# V1_1001_REV2.net
KiCad netlist of a schematic drawn in Altium Designer
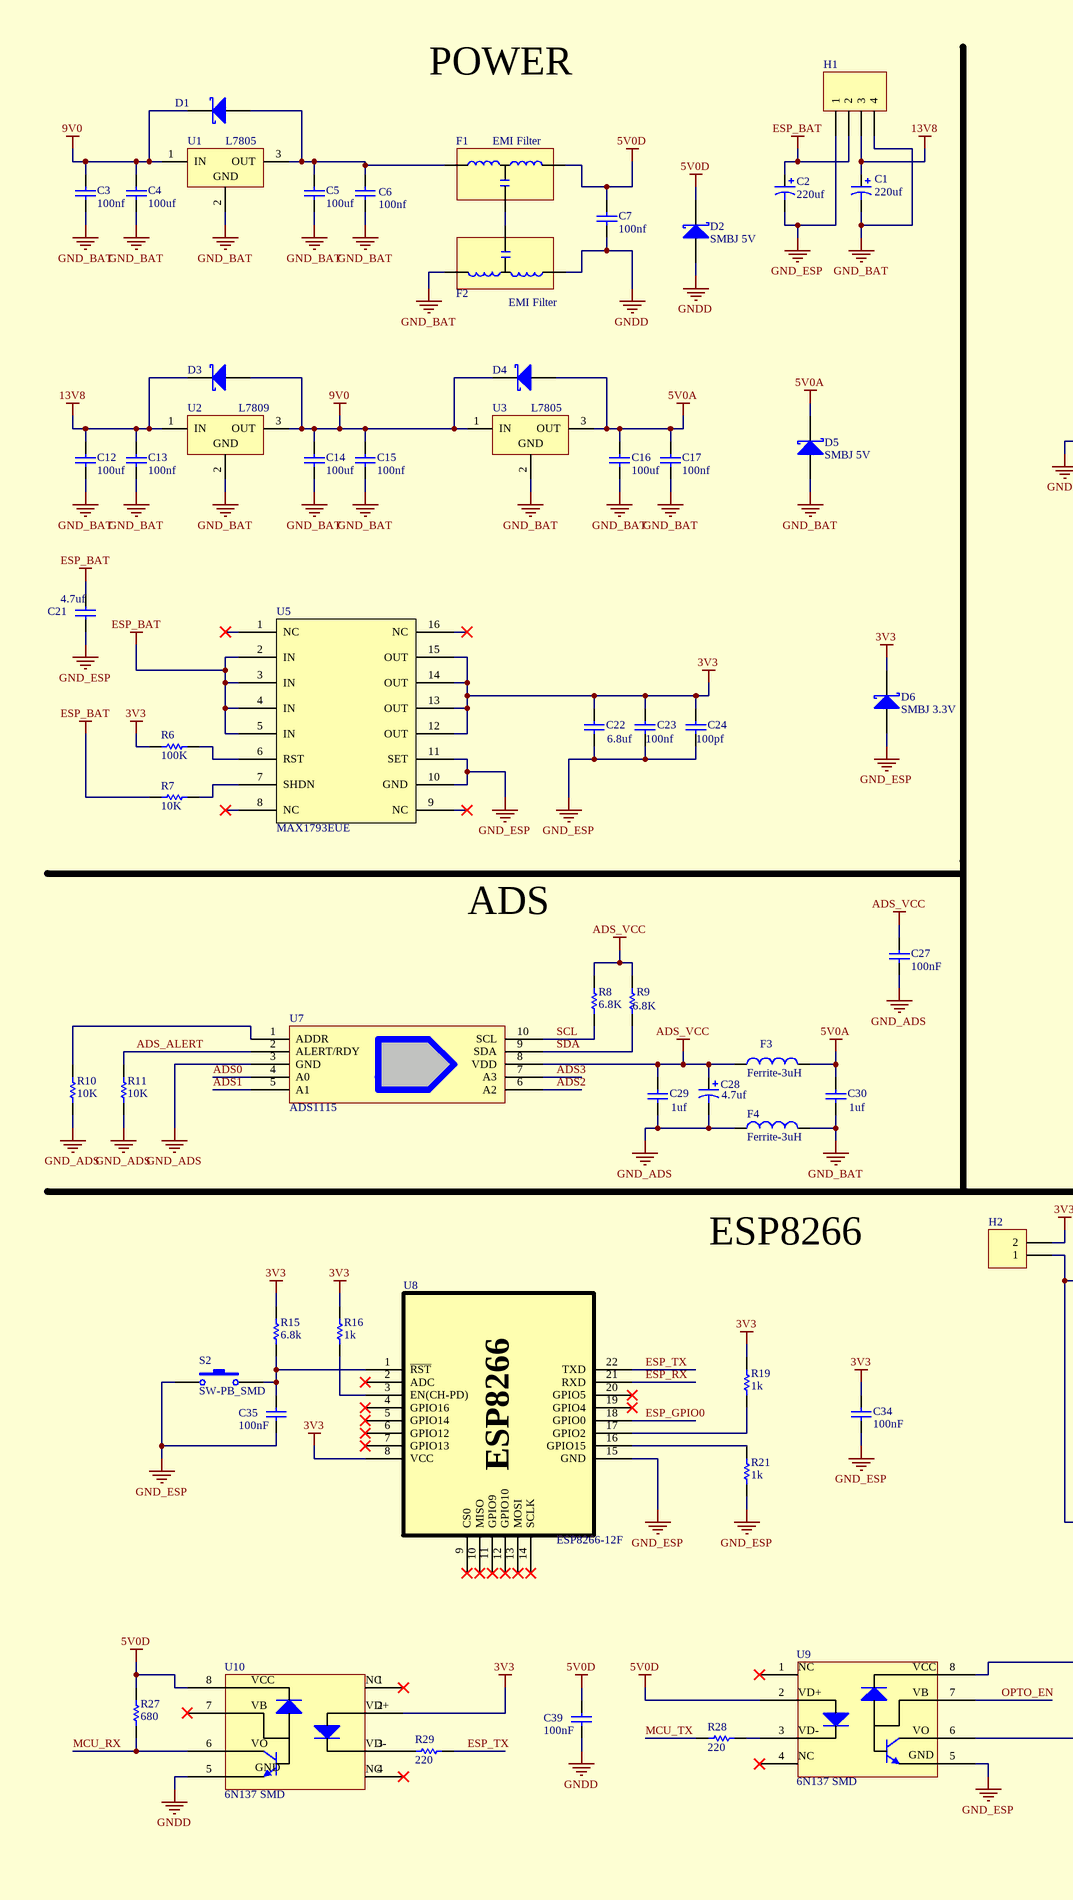
[diagram p0: V1_1001_REV2.SchDoc, left]
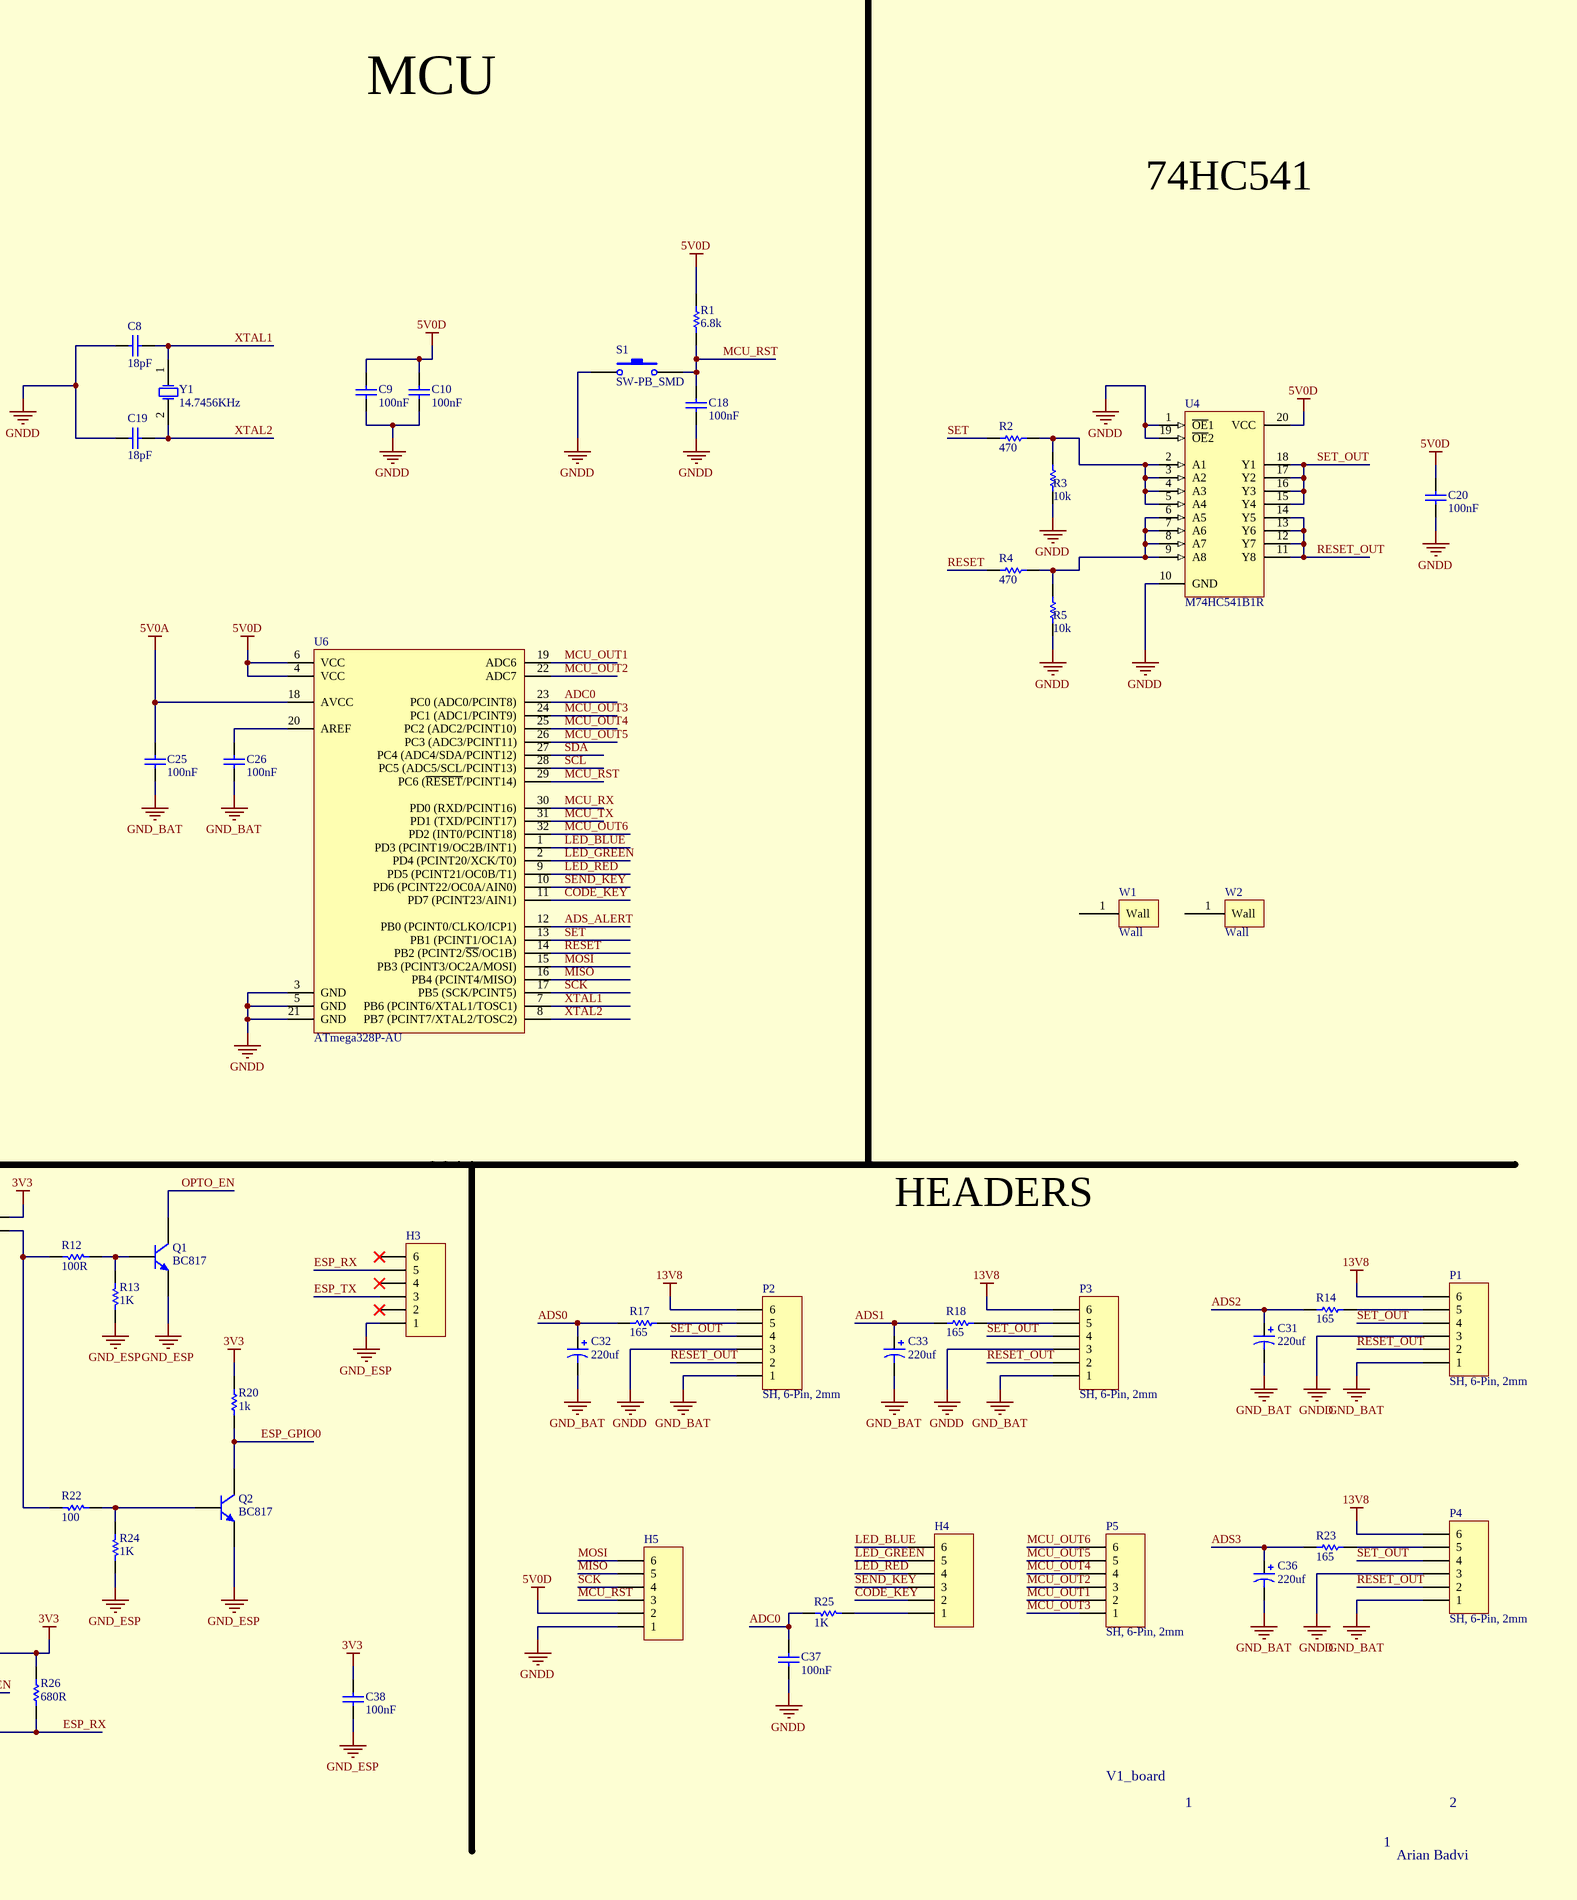
[diagram p1: V1_1001_REV2.SchDoc, right]

(export (version "E")
  (design (tool "Eeschema 10.0.6"))
  (components
    (comp (ref "C1")
      (value "220uf")
      (footprint "C_CYL_SMD2")
      (description "pol cap, Ele")
      (libsource (lib "Library") (part "Cap Pol"))
    )
    (comp (ref "C2")
      (value "220uf")
      (footprint "C_CYL_SMD2")
      (description "pol cap, Ele")
      (libsource (lib "Library") (part "Cap Pol"))
    )
    (comp (ref "C3")
      (value "100nf")
      (footprint "1206")
      (description "Capacitor, 1206")
      (libsource (lib "Miscellaneous Devices") (part "Cap"))
    )
    (comp (ref "C4")
      (value "100uf")
      (footprint "1206")
      (description "Capacitor, 1206")
      (libsource (lib "Miscellaneous Devices") (part "Cap"))
    )
    (comp (ref "C5")
      (value "100uf")
      (footprint "1206")
      (description "Capacitor, 1206")
      (libsource (lib "Miscellaneous Devices") (part "Cap"))
    )
    (comp (ref "C6")
      (value "100nf")
      (footprint "1206")
      (description "Capacitor, 1206")
      (libsource (lib "Miscellaneous Devices") (part "Cap"))
    )
    (comp (ref "C7")
      (value "100nf")
      (footprint "1206")
      (description "Capacitor, 1206")
      (libsource (lib "Miscellaneous Devices") (part "Cap"))
    )
    (comp (ref "C8")
      (value "18pF")
      (footprint "1206")
      (description "Capacitor")
      (libsource (lib "Miscellaneous Devices") (part "Cap"))
    )
    (comp (ref "C9")
      (value "100nF")
      (footprint "1206")
      (description "Capacitor")
      (libsource (lib "Miscellaneous Devices") (part "Cap"))
    )
    (comp (ref "C10")
      (value "100nF")
      (footprint "1206")
      (description "Capacitor")
      (libsource (lib "Miscellaneous Devices") (part "Cap"))
    )
    (comp (ref "C12")
      (value "100uf")
      (footprint "1206")
      (description "Capacitor, 1206")
      (libsource (lib "Miscellaneous Devices") (part "Cap"))
    )
    (comp (ref "C13")
      (value "100nf")
      (footprint "1206")
      (description "Capacitor, 1206")
      (libsource (lib "Miscellaneous Devices") (part "Cap"))
    )
    (comp (ref "C14")
      (value "100uf")
      (footprint "1206")
      (description "Capacitor, 1206")
      (libsource (lib "Miscellaneous Devices") (part "Cap"))
    )
    (comp (ref "C15")
      (value "100nf")
      (footprint "1206")
      (description "Capacitor, 1206")
      (libsource (lib "Miscellaneous Devices") (part "Cap"))
    )
    (comp (ref "C16")
      (value "100uf")
      (footprint "1206")
      (description "Capacitor, 1206")
      (libsource (lib "Miscellaneous Devices") (part "Cap"))
    )
    (comp (ref "C17")
      (value "100nf")
      (footprint "1206")
      (description "Capacitor, 1206")
      (libsource (lib "Miscellaneous Devices") (part "Cap"))
    )
    (comp (ref "C18")
      (value "100nF")
      (footprint "1206")
      (description "Capacitor")
      (libsource (lib "Miscellaneous Devices") (part "Cap"))
    )
    (comp (ref "C19")
      (value "18pF")
      (footprint "1206")
      (description "Capacitor")
      (libsource (lib "Miscellaneous Devices") (part "Cap"))
    )
    (comp (ref "C20")
      (value "100nF")
      (footprint "1206")
      (description "Capacitor, 1206, 100nf")
      (libsource (lib "Miscellaneous Devices") (part "Cap"))
    )
    (comp (ref "C21")
      (value "4.7uf")
      (footprint "1206")
      (description "Capacitor, 1206")
      (libsource (lib "Library") (part "Cap"))
    )
    (comp (ref "C22")
      (value "6.8uf")
      (footprint "1206")
      (description "Capacitor, 1206")
      (libsource (lib "Library") (part "Cap"))
    )
    (comp (ref "C23")
      (value "100nf")
      (footprint "1206")
      (description "Capacitor, 1206")
      (libsource (lib "Library") (part "Cap"))
    )
    (comp (ref "C24")
      (value "100pf")
      (footprint "1206")
      (description "Capacitor, 1206")
      (libsource (lib "Library") (part "Cap"))
    )
    (comp (ref "C25")
      (value "100nF")
      (footprint "1206")
      (description "Capacitor")
      (libsource (lib "Miscellaneous Devices") (part "Cap"))
    )
    (comp (ref "C26")
      (value "100nF")
      (footprint "1206")
      (description "Capacitor")
      (libsource (lib "Miscellaneous Devices") (part "Cap"))
    )
    (comp (ref "C27")
      (value "100nF")
      (footprint "1206")
      (description "Capacitor")
      (libsource (lib "Miscellaneous Devices") (part "Cap"))
    )
    (comp (ref "C28")
      (value "4.7uf")
      (footprint "CAP_SMD_A")
      (description "Tantalium Capacitor")
      (libsource (lib "Library") (part "Cap Pol"))
    )
    (comp (ref "C29")
      (value "1uf")
      (footprint "1206")
      (description "Capacitor, 1206")
      (libsource (lib "Library") (part "Cap"))
    )
    (comp (ref "C30")
      (value "1uf")
      (footprint "1206")
      (description "Capacitor, 1206")
      (libsource (lib "Library") (part "Cap"))
    )
    (comp (ref "C31")
      (value "220uf")
      (footprint "CAP_SMD_D")
      (description "pol cap, tan")
      (libsource (lib "Library") (part "Cap Pol"))
    )
    (comp (ref "C32")
      (value "220uf")
      (footprint "CAP_SMD_D")
      (description "pol cap, tan")
      (libsource (lib "Library") (part "Cap Pol"))
    )
    (comp (ref "C33")
      (value "220uf")
      (footprint "CAP_SMD_D")
      (description "pol cap, tan")
      (libsource (lib "Library") (part "Cap Pol"))
    )
    (comp (ref "C34")
      (value "100nF")
      (footprint "1206")
      (description "Capacitor")
      (libsource (lib "Miscellaneous Devices") (part "Cap"))
    )
    (comp (ref "C35")
      (value "100nF")
      (footprint "1206")
      (description "Capacitor")
      (libsource (lib "Miscellaneous Devices") (part "Cap"))
    )
    (comp (ref "C36")
      (value "220uf")
      (footprint "CAP_SMD_D")
      (description "pol cap, tan")
      (libsource (lib "Library") (part "Cap Pol"))
    )
    (comp (ref "C37")
      (value "100nF")
      (footprint "1206")
      (description "Capacitor")
      (libsource (lib "Miscellaneous Devices") (part "Cap"))
    )
    (comp (ref "C38")
      (value "100nF")
      (footprint "1206")
      (description "Capacitor")
      (libsource (lib "Miscellaneous Devices") (part "Cap"))
    )
    (comp (ref "C39")
      (value "100nF")
      (footprint "1206")
      (description "Capacitor, 1206")
      (libsource (lib "Miscellaneous Devices") (part "Cap"))
    )
    (comp (ref "D1")
      (value "D Schottky")
      (footprint "ZINER")
      (description "Schottky Diode, 1N4148")
      (libsource (lib "Miscellaneous Devices") (part "D Schottky"))
    )
    (comp (ref "D2")
      (value "SMBJ 5V")
      (footprint "TVS")
      (description "Schottky Rectifier")
      (libsource (lib "Miscellaneous Devices") (part "Diode 18TQ045"))
    )
    (comp (ref "D3")
      (value "D Schottky")
      (footprint "ZINER")
      (description "Schottky Diode, 1N4148")
      (libsource (lib "Miscellaneous Devices") (part "D Schottky"))
    )
    (comp (ref "D4")
      (value "D Schottky")
      (footprint "ZINER")
      (description "Schottky Diode, 1N4148")
      (libsource (lib "Miscellaneous Devices") (part "D Schottky"))
    )
    (comp (ref "D5")
      (value "SMBJ 5V")
      (footprint "TVS")
      (description "Schottky Rectifier")
      (libsource (lib "Miscellaneous Devices") (part "Diode 18TQ045"))
    )
    (comp (ref "D6")
      (value "SMBJ 3.3V")
      (footprint "TVS")
      (description "Schottky Rectifier")
      (libsource (lib "Miscellaneous Devices") (part "Diode 18TQ045"))
    )
    (comp (ref "F1")
      (value "EMI Filter")
      (footprint "HDR1X3")
      (libsource (lib "Library_v2") (part "EMI Filter"))
    )
    (comp (ref "F2") (value "EMI Filter") (footprint "HDR1X3") (libsource (lib "") (part "EMI Filter_1")))
    (comp (ref "F3")
      (value "Ferrite-3uH")
      (footprint "1206")
      (description "Inductor")
      (libsource (lib "Miscellaneous Devices") (part "Inductor"))
    )
    (comp (ref "F4")
      (value "Ferrite-3uH")
      (footprint "1206")
      (description "Inductor")
      (libsource (lib "Miscellaneous Devices") (part "Inductor"))
    )
    (comp (ref "H1")
      (value "White Connector 4pin")
      (footprint "XH_4_me")
      (libsource (lib "Miscellaneous Connectors") (part "Header 4"))
    )
    (comp (ref "H2")
      (value "Pin Header, 1.27")
      (footprint "H1.27")
      (description "Header, 2-Pin, 1.27mm")
      (libsource (lib "Miscellaneous Connectors") (part "Header 2"))
    )
    (comp (ref "H3")
      (value "White SMD Connector 6pin")
      (footprint "White SMD Connector 6pin B")
      (libsource (lib "Miscellaneous Connectors") (part "Header 6"))
    )
    (comp (ref "H4")
      (value "White SMD Connector 6pin")
      (footprint "White SMD Connector 6pin B")
      (libsource (lib "Miscellaneous Connectors") (part "Header 6"))
    )
    (comp (ref "H5")
      (value "White SMD Connector 6pin")
      (footprint "White SMD Connector 6pin B")
      (libsource (lib "Miscellaneous Connectors") (part "Header 6"))
    )
    (comp (ref "P1")
      (value "SH, 6-Pin, 2mm")
      (footprint "PH_6_ME")
      (libsource (lib "Miscellaneous Connectors") (part "Header 6"))
    )
    (comp (ref "P2")
      (value "SH, 6-Pin, 2mm")
      (footprint "PH_6_ME")
      (libsource (lib "Miscellaneous Connectors") (part "Header 6"))
    )
    (comp (ref "P3")
      (value "SH, 6-Pin, 2mm")
      (footprint "PH_6_ME")
      (libsource (lib "Miscellaneous Connectors") (part "Header 6"))
    )
    (comp (ref "P4")
      (value "SH, 6-Pin, 2mm")
      (footprint "PH_6_ME")
      (libsource (lib "Miscellaneous Connectors") (part "Header 6"))
    )
    (comp (ref "P5")
      (value "SH, 6-Pin, 2mm")
      (footprint "PH_6_ME")
      (libsource (lib "Miscellaneous Connectors") (part "Header 6"))
    )
    (comp (ref "Q1")
      (value "BC817")
      (footprint "sot23")
      (description "General Purpose Transistor NPN Silicon")
      (libsource (lib "Motorola Discrete BJT") (part "2N2222"))
    )
    (comp (ref "Q2")
      (value "BC817")
      (footprint "sot23")
      (description "General Purpose Transistor NPN Silicon")
      (libsource (lib "Motorola Discrete BJT") (part "2N2222"))
    )
    (comp (ref "R1")
      (value "6.8k")
      (footprint "1206")
      (description "Resistor, 6.8k")
      (libsource (lib "Miscellaneous Devices") (part "Res1"))
    )
    (comp (ref "R2")
      (value "470")
      (footprint "1206")
      (description "Resistor, 1206, 4.7k")
      (libsource (lib "Miscellaneous Devices") (part "Res1"))
    )
    (comp (ref "R3")
      (value "10k")
      (footprint "1206")
      (description "Resistor, 1206, 4.7k")
      (libsource (lib "Miscellaneous Devices") (part "Res1"))
    )
    (comp (ref "R4")
      (value "470")
      (footprint "1206")
      (description "Resistor, 1206, 4.7k")
      (libsource (lib "Miscellaneous Devices") (part "Res1"))
    )
    (comp (ref "R5")
      (value "10k")
      (footprint "1206")
      (description "Resistor, 1206, 4.7k")
      (libsource (lib "Miscellaneous Devices") (part "Res1"))
    )
    (comp (ref "R6")
      (value "100K")
      (footprint "1206")
      (description "General Resistor")
      (libsource (lib "Library") (part "Resistor"))
    )
    (comp (ref "R7")
      (value "10K")
      (footprint "1206")
      (description "General Resistor")
      (libsource (lib "Library") (part "Resistor"))
    )
    (comp (ref "R8")
      (value "6.8K")
      (footprint "1206")
      (description "General Resistor")
      (libsource (lib "Library") (part "Resistor"))
    )
    (comp (ref "R9")
      (value "6.8K")
      (footprint "1206")
      (description "General Resistor")
      (libsource (lib "Library") (part "Resistor"))
    )
    (comp (ref "R10")
      (value "10K")
      (footprint "1206")
      (description "General Resistor")
      (libsource (lib "Library") (part "Resistor"))
    )
    (comp (ref "R11")
      (value "10K")
      (footprint "1206")
      (description "General Resistor")
      (libsource (lib "Library") (part "Resistor"))
    )
    (comp (ref "R12")
      (value "100R")
      (footprint "1206")
      (description "General Resistor")
      (libsource (lib "Library") (part "Resistor"))
    )
    (comp (ref "R13")
      (value "1K")
      (footprint "1206")
      (description "General Resistor")
      (libsource (lib "Library") (part "Resistor"))
    )
    (comp (ref "R14")
      (value "165")
      (footprint "1206")
      (description "Resistor, 1206")
      (libsource (lib "Miscellaneous Devices") (part "Res1"))
    )
    (comp (ref "R15")
      (value "6.8k")
      (footprint "1206")
      (description "Resistor, 6.8k")
      (libsource (lib "Miscellaneous Devices") (part "Res1"))
    )
    (comp (ref "R16")
      (value "1k")
      (footprint "1206")
      (description "Resistor")
      (libsource (lib "Miscellaneous Devices") (part "Res1"))
    )
    (comp (ref "R17")
      (value "165")
      (footprint "1206")
      (description "Resistor, 1206")
      (libsource (lib "Miscellaneous Devices") (part "Res1"))
    )
    (comp (ref "R18")
      (value "165")
      (footprint "1206")
      (description "Resistor, 1206")
      (libsource (lib "Miscellaneous Devices") (part "Res1"))
    )
    (comp (ref "R19")
      (value "1k")
      (footprint "1206")
      (description "Resistor")
      (libsource (lib "Miscellaneous Devices") (part "Res1"))
    )
    (comp (ref "R20")
      (value "1k")
      (footprint "1206")
      (description "Resistor")
      (libsource (lib "Miscellaneous Devices") (part "Res1"))
    )
    (comp (ref "R21")
      (value "1k")
      (footprint "1206")
      (description "Resistor")
      (libsource (lib "Miscellaneous Devices") (part "Res1"))
    )
    (comp (ref "R22")
      (value "100")
      (footprint "1206")
      (description "General Resistor")
      (libsource (lib "Library") (part "Resistor"))
    )
    (comp (ref "R23")
      (value "165")
      (footprint "1206")
      (description "Resistor, 1206")
      (libsource (lib "Miscellaneous Devices") (part "Res1"))
    )
    (comp (ref "R24")
      (value "1K")
      (footprint "1206")
      (description "General Resistor")
      (libsource (lib "") (part "Resistor_1"))
    )
    (comp (ref "R25")
      (value "1K")
      (footprint "1206")
      (description "General Resistor")
      (libsource (lib "Library") (part "Resistor"))
    )
    (comp (ref "R26")
      (value "680R")
      (footprint "1206")
      (description "General Resistor")
      (libsource (lib "Library") (part "Resistor"))
    )
    (comp (ref "R27")
      (value "680")
      (footprint "1206")
      (description "Resistor, 6.8k")
      (libsource (lib "Miscellaneous Devices") (part "Res1"))
    )
    (comp (ref "R28")
      (value "220")
      (footprint "1206")
      (description "General Resistor")
      (libsource (lib "Library") (part "Resistor"))
    )
    (comp (ref "R29")
      (value "220")
      (footprint "1206")
      (description "General Resistor")
      (libsource (lib "Library") (part "Resistor"))
    )
    (comp (ref "S1")
      (value "SW-PB_SMD")
      (footprint "PB4x3.2")
      (description "Switch")
      (libsource (lib "Miscellaneous Devices") (part "SW-PB"))
    )
    (comp (ref "S2")
      (value "SW-PB_SMD")
      (footprint "PB4x3.2")
      (description "Switch")
      (libsource (lib "Miscellaneous Devices") (part "SW-PB"))
    )
    (comp (ref "U1")
      (value "L7805")
      (footprint "DPAK")
      (description "Positive Voltage Regulator")
      (libsource (lib "ST Power Mgt Voltage Regulator") (part "L7805CD2T"))
    )
    (comp (ref "U2")
      (value "L7809")
      (footprint "DPAK")
      (description "Positive Voltage Regulator")
      (libsource (lib "ST Power Mgt Voltage Regulator") (part "L7805CD2T"))
    )
    (comp (ref "U3")
      (value "L7805")
      (footprint "DPAK")
      (description "Positive Voltage Regulator")
      (libsource (lib "ST Power Mgt Voltage Regulator") (part "L7805CD2T"))
    )
    (comp (ref "U4")
      (value "M74HC541B1R")
      (footprint "TSSOP20")
      (description "Octal Bus Buffer with 3 State Outputs (Non Inverted)")
      (libsource (lib "ST Logic Buffer Line Driver") (part "M74HC541B1R"))
    )
    (comp (ref "U5") (value "MAX1793EUE") (footprint "TSSOP16") (libsource (lib "Library") (part "MAX1793")))
    (comp (ref "U6")
      (value "ATmega328P-AU")
      (footprint "32A_L")
      (libsource (lib "Library") (part "ATmega328P-AU"))
    )
    (comp (ref "U7") (value "ADS1115") (footprint "TSSOP10_N") (libsource (lib "Library") (part "ADS1115")))
    (comp (ref "U8")
      (value "ESP8266-12F")
      (footprint "esp8266 esp-12-e")
      (libsource (lib "ESP8266") (part "ESP8266"))
    )
    (comp (ref "U9") (value "6N137 SMD") (footprint "SMD8") (libsource (lib "Library") (part "6N137")))
    (comp (ref "U10") (value "6N137 SMD") (footprint "SMD8") (libsource (lib "") (part "6N137_1")))
    (comp (ref "W1") (value "Wall") (footprint "Wall") (libsource (lib "Library") (part "Wall")))
    (comp (ref "W2") (value "Wall") (footprint "Wall") (libsource (lib "Library") (part "Wall")))
    (comp (ref "Y1")
      (value "14.7456KHz")
      (footprint "XTAL_SMD")
      (description "Crystal Oscillator, 14.7456KHz")
      (libsource (lib "Miscellaneous Devices") (part "XTAL"))
    )
  )
  (nets
    (net (code "1") (name "/ADC0") (class "Default")
      (node (ref "C37") (pin "2") (pinfunction "2_2") (pintype "passive"))
      (node (ref "R25") (pin "1") (pinfunction "1_1") (pintype "passive"))
      (node (ref "U6") (pin "23") (pinfunction "PC0_(ADC0/PCINT8)_23") (pintype "passive"))
    )
    (net (code "2") (name "/ADS0") (class "Default")
      (node (ref "C32") (pin "1") (pinfunction "1_1") (pintype "passive"))
      (node (ref "R17") (pin "2") (pinfunction "2_2") (pintype "passive"))
      (node (ref "U7") (pin "4") (pinfunction "A0_4") (pintype "passive"))
    )
    (net (code "3") (name "/ADS1") (class "Default")
      (node (ref "C33") (pin "1") (pinfunction "1_1") (pintype "passive"))
      (node (ref "R18") (pin "2") (pinfunction "2_2") (pintype "passive"))
      (node (ref "U7") (pin "5") (pinfunction "A1_5") (pintype "passive"))
    )
    (net (code "4") (name "/ADS2") (class "Default")
      (node (ref "C31") (pin "1") (pinfunction "1_1") (pintype "passive"))
      (node (ref "R14") (pin "2") (pinfunction "2_2") (pintype "passive"))
      (node (ref "U7") (pin "6") (pinfunction "A2_6") (pintype "passive"))
    )
    (net (code "5") (name "/ADS3") (class "Default")
      (node (ref "C36") (pin "1") (pinfunction "1_1") (pintype "passive"))
      (node (ref "R23") (pin "2") (pinfunction "2_2") (pintype "passive"))
      (node (ref "U7") (pin "7") (pinfunction "A3_7") (pintype "passive"))
    )
    (net (code "6") (name "/ADS_ALERT") (class "Default")
      (node (ref "R11") (pin "2") (pinfunction "2_2") (pintype "passive"))
      (node (ref "U6") (pin "12") (pinfunction "PB0_(PCINT0/CLKO/ICP1)_12") (pintype "passive"))
      (node (ref "U7") (pin "2") (pinfunction "ALERT/RDY_2") (pintype "passive"))
    )
    (net (code "7") (name "/CODE_KEY") (class "Default")
      (node (ref "H4") (pin "2") (pinfunction "2_2") (pintype "passive"))
      (node (ref "U6") (pin "11") (pinfunction "PD7_(PCINT23/AIN1)_11") (pintype "passive"))
    )
    (net (code "8") (name "/ESP_GPIO0") (class "Default")
      (node (ref "Q2") (pin "3") (pinfunction "C_3") (pintype "passive"))
      (node (ref "R20") (pin "2") (pinfunction "2_2") (pintype "passive"))
      (node (ref "U8") (pin "18") (pinfunction "GPIO0_18") (pintype "passive"))
    )
    (net (code "9") (name "/ESP_RX") (class "Default")
      (node (ref "H3") (pin "5") (pinfunction "5_5") (pintype "passive"))
      (node (ref "R26") (pin "1") (pinfunction "1_1") (pintype "passive"))
      (node (ref "U8") (pin "21") (pinfunction "RXD_21") (pintype "passive"))
      (node (ref "U9") (pin "6") (pinfunction "6_6") (pintype "passive"))
    )
    (net (code "10") (name "/ESP_TX") (class "Default")
      (node (ref "H3") (pin "3") (pinfunction "3_3") (pintype "passive"))
      (node (ref "R29") (pin "2") (pinfunction "2_2") (pintype "passive"))
      (node (ref "U8") (pin "22") (pinfunction "TXD_22") (pintype "passive"))
    )
    (net (code "11") (name "/LED_BLUE") (class "Default")
      (node (ref "H4") (pin "6") (pinfunction "6_6") (pintype "passive"))
      (node (ref "U6") (pin "1") (pinfunction "PD3_(PCINT19/OC2B/INT1)_1") (pintype "passive"))
    )
    (net (code "12") (name "/LED_GREEN") (class "Default")
      (node (ref "H4") (pin "5") (pinfunction "5_5") (pintype "passive"))
      (node (ref "U6") (pin "2") (pinfunction "PD4_(PCINT20/XCK/T0)_2") (pintype "passive"))
    )
    (net (code "13") (name "/LED_RED") (class "Default")
      (node (ref "H4") (pin "4") (pinfunction "4_4") (pintype "passive"))
      (node (ref "U6") (pin "9") (pinfunction "PD5_(PCINT21/OC0B/T1)_9") (pintype "passive"))
    )
    (net (code "14") (name "/MCU_OUT1") (class "Default")
      (node (ref "P5") (pin "2") (pinfunction "2_2") (pintype "passive"))
      (node (ref "U6") (pin "19") (pinfunction "ADC6_19") (pintype "passive"))
    )
    (net (code "15") (name "/MCU_OUT2") (class "Default")
      (node (ref "P5") (pin "3") (pinfunction "3_3") (pintype "passive"))
      (node (ref "U6") (pin "22") (pinfunction "ADC7_22") (pintype "passive"))
    )
    (net (code "16") (name "/MCU_OUT3") (class "Default")
      (node (ref "P5") (pin "1") (pinfunction "1_1") (pintype "passive"))
      (node (ref "U6") (pin "24") (pinfunction "PC1_(ADC1/PCINT9)_24") (pintype "passive"))
    )
    (net (code "17") (name "/MCU_OUT4") (class "Default")
      (node (ref "P5") (pin "4") (pinfunction "4_4") (pintype "passive"))
      (node (ref "U6") (pin "25") (pinfunction "PC2_(ADC2/PCINT10)_25") (pintype "passive"))
    )
    (net (code "18") (name "/MCU_OUT5") (class "Default")
      (node (ref "P5") (pin "5") (pinfunction "5_5") (pintype "passive"))
      (node (ref "U6") (pin "26") (pinfunction "PC3_(ADC3/PCINT11)_26") (pintype "passive"))
    )
    (net (code "19") (name "/MCU_OUT6") (class "Default")
      (node (ref "P5") (pin "6") (pinfunction "6_6") (pintype "passive"))
      (node (ref "U6") (pin "32") (pinfunction "PD2_(INT0/PCINT18)_32") (pintype "passive"))
    )
    (net (code "20") (name "/MCU_RST") (class "Default")
      (node (ref "C18") (pin "2") (pinfunction "2_2") (pintype "passive"))
      (node (ref "H5") (pin "3") (pinfunction "3_3") (pintype "passive"))
      (node (ref "R1") (pin "2") (pinfunction "2_2") (pintype "passive"))
      (node (ref "S1") (pin "2") (pinfunction "2_2") (pintype "passive"))
      (node (ref "U6") (pin "29") (pinfunction "PC6_(~{RESET}/PCINT14)_29") (pintype "passive"))
    )
    (net (code "21") (name "/MCU_RX") (class "Default")
      (node (ref "R27") (pin "2") (pinfunction "2_2") (pintype "passive"))
      (node (ref "U10") (pin "6") (pinfunction "6_6") (pintype "passive"))
      (node (ref "U6") (pin "30") (pinfunction "PD0_(RXD/PCINT16)_30") (pintype "passive"))
    )
    (net (code "22") (name "/MCU_TX") (class "Default")
      (node (ref "R28") (pin "1") (pinfunction "1_1") (pintype "passive"))
      (node (ref "U6") (pin "31") (pinfunction "PD1_(TXD/PCINT17)_31") (pintype "passive"))
    )
    (net (code "23") (name "/MISO") (class "Default")
      (node (ref "H5") (pin "5") (pinfunction "5_5") (pintype "passive"))
      (node (ref "U6") (pin "16") (pinfunction "PB4_(PCINT4/MISO)_16") (pintype "passive"))
    )
    (net (code "24") (name "/MOSI") (class "Default")
      (node (ref "H5") (pin "6") (pinfunction "6_6") (pintype "passive"))
      (node (ref "U6") (pin "15") (pinfunction "PB3_(PCINT3/OC2A/MOSI)_15") (pintype "passive"))
    )
    (net (code "25") (name "/OPTO_EN") (class "Default")
      (node (ref "Q1") (pin "3") (pinfunction "C_3") (pintype "passive"))
      (node (ref "U9") (pin "7") (pinfunction "7_7") (pintype "passive"))
    )
    (net (code "26") (name "/RESET") (class "Default")
      (node (ref "R4") (pin "2") (pinfunction "2_2") (pintype "passive"))
      (node (ref "U6") (pin "14") (pinfunction "PB2_(PCINT2/~{SS}/OC1B)_14") (pintype "passive"))
    )
    (net (code "27") (name "/RESET_OUT") (class "Default")
      (node (ref "P1") (pin "2") (pinfunction "2_2") (pintype "passive"))
      (node (ref "P2") (pin "2") (pinfunction "2_2") (pintype "passive"))
      (node (ref "P3") (pin "2") (pinfunction "2_2") (pintype "passive"))
      (node (ref "P4") (pin "2") (pinfunction "2_2") (pintype "passive"))
      (node (ref "U4") (pin "11") (pinfunction "Y8_11") (pintype "tri_state"))
      (node (ref "U4") (pin "12") (pinfunction "Y7_12") (pintype "tri_state"))
      (node (ref "U4") (pin "13") (pinfunction "Y6_13") (pintype "tri_state"))
      (node (ref "U4") (pin "14") (pinfunction "Y5_14") (pintype "tri_state"))
    )
    (net (code "28") (name "/SCK") (class "Default")
      (node (ref "H5") (pin "4") (pinfunction "4_4") (pintype "passive"))
      (node (ref "U6") (pin "17") (pinfunction "PB5_(SCK/PCINT5)_17") (pintype "passive"))
    )
    (net (code "29") (name "/SCL") (class "Default")
      (node (ref "R8") (pin "2") (pinfunction "2_2") (pintype "passive"))
      (node (ref "U6") (pin "28") (pinfunction "PC5_(ADC5/SCL/PCINT13)_28") (pintype "passive"))
      (node (ref "U7") (pin "10") (pinfunction "SCL_10") (pintype "passive"))
    )
    (net (code "30") (name "/SDA") (class "Default")
      (node (ref "R9") (pin "2") (pinfunction "2_2") (pintype "passive"))
      (node (ref "U6") (pin "27") (pinfunction "PC4_(ADC4/SDA/PCINT12)_27") (pintype "passive"))
      (node (ref "U7") (pin "9") (pinfunction "SDA_9") (pintype "passive"))
    )
    (net (code "31") (name "/SEND_KEY") (class "Default")
      (node (ref "H4") (pin "3") (pinfunction "3_3") (pintype "passive"))
      (node (ref "U6") (pin "10") (pinfunction "PD6_(PCINT22/OC0A/AIN0)_10") (pintype "passive"))
    )
    (net (code "32") (name "/SET") (class "Default")
      (node (ref "R2") (pin "2") (pinfunction "2_2") (pintype "passive"))
      (node (ref "U6") (pin "13") (pinfunction "PB1_(PCINT1/OC1A)_13") (pintype "passive"))
    )
    (net (code "33") (name "/SET_OUT") (class "Default")
      (node (ref "P1") (pin "4") (pinfunction "4_4") (pintype "passive"))
      (node (ref "P2") (pin "4") (pinfunction "4_4") (pintype "passive"))
      (node (ref "P3") (pin "4") (pinfunction "4_4") (pintype "passive"))
      (node (ref "P4") (pin "4") (pinfunction "4_4") (pintype "passive"))
      (node (ref "U4") (pin "15") (pinfunction "Y4_15") (pintype "tri_state"))
      (node (ref "U4") (pin "16") (pinfunction "Y3_16") (pintype "tri_state"))
      (node (ref "U4") (pin "17") (pinfunction "Y2_17") (pintype "tri_state"))
      (node (ref "U4") (pin "18") (pinfunction "Y1_18") (pintype "tri_state"))
    )
    (net (code "34") (name "/XTAL1") (class "Default")
      (node (ref "C8") (pin "2") (pinfunction "2_2") (pintype "passive"))
      (node (ref "U6") (pin "7") (pinfunction "PB6_(PCINT6/XTAL1/TOSC1)_7") (pintype "passive"))
      (node (ref "Y1") (pin "1") (pinfunction "OSC1_1") (pintype "passive"))
    )
    (net (code "35") (name "/XTAL2") (class "Default")
      (node (ref "C19") (pin "2") (pinfunction "2_2") (pintype "passive"))
      (node (ref "U6") (pin "8") (pinfunction "PB7_(PCINT7/XTAL2/TOSC2)_8") (pintype "passive"))
      (node (ref "Y1") (pin "2") (pinfunction "OSC2_2") (pintype "passive"))
    )
    (net (code "36") (name "3V3") (class "Default")
      (node (ref "C22") (pin "2") (pinfunction "2_2") (pintype "passive"))
      (node (ref "C23") (pin "2") (pinfunction "2_2") (pintype "passive"))
      (node (ref "C24") (pin "2") (pinfunction "2_2") (pintype "passive"))
      (node (ref "C34") (pin "2") (pinfunction "2_2") (pintype "passive"))
      (node (ref "C38") (pin "2") (pinfunction "2_2") (pintype "passive"))
      (node (ref "D6") (pin "1") (pinfunction "K_1") (pintype "passive"))
      (node (ref "H2") (pin "2") (pinfunction "2_2") (pintype "passive"))
      (node (ref "R15") (pin "1") (pinfunction "1_1") (pintype "passive"))
      (node (ref "R16") (pin "2") (pinfunction "2_2") (pintype "passive"))
      (node (ref "R19") (pin "2") (pinfunction "2_2") (pintype "passive"))
      (node (ref "R20") (pin "1") (pinfunction "1_1") (pintype "passive"))
      (node (ref "R26") (pin "2") (pinfunction "2_2") (pintype "passive"))
      (node (ref "R6") (pin "2") (pinfunction "2_2") (pintype "passive"))
      (node (ref "U10") (pin "2") (pinfunction "2_2") (pintype "passive"))
      (node (ref "U5") (pin "12") (pinfunction "OUT_12") (pintype "passive"))
      (node (ref "U5") (pin "13") (pinfunction "OUT_13") (pintype "passive"))
      (node (ref "U5") (pin "14") (pinfunction "OUT_14") (pintype "passive"))
      (node (ref "U5") (pin "15") (pinfunction "OUT_15") (pintype "passive"))
      (node (ref "U8") (pin "8") (pinfunction "VCC_8") (pintype "passive"))
      (node (ref "U9") (pin "8") (pinfunction "8_8") (pintype "passive"))
    )
    (net (code "37") (name "5V0A") (class "Default")
      (node (ref "C16") (pin "2") (pinfunction "2_2") (pintype "passive"))
      (node (ref "C17") (pin "2") (pinfunction "2_2") (pintype "passive"))
      (node (ref "C25") (pin "2") (pinfunction "2_2") (pintype "passive"))
      (node (ref "C30") (pin "2") (pinfunction "2_2") (pintype "passive"))
      (node (ref "D4") (pin "1") (pinfunction "A_1") (pintype "passive"))
      (node (ref "D5") (pin "1") (pinfunction "K_1") (pintype "passive"))
      (node (ref "F3") (pin "2") (pinfunction "2_2") (pintype "passive"))
      (node (ref "U3") (pin "3") (pinfunction "OUT_3") (pintype "power_in"))
      (node (ref "U6") (pin "18") (pinfunction "AVCC_18") (pintype "passive"))
    )
    (net (code "38") (name "5V0D") (class "Default")
      (node (ref "C10") (pin "2") (pinfunction "2_2") (pintype "passive"))
      (node (ref "C20") (pin "1") (pinfunction "1_1") (pintype "passive"))
      (node (ref "C39") (pin "2") (pinfunction "2_2") (pintype "passive"))
      (node (ref "C7") (pin "2") (pinfunction "2_2") (pintype "passive"))
      (node (ref "C9") (pin "2") (pinfunction "2_2") (pintype "passive"))
      (node (ref "D2") (pin "1") (pinfunction "K_1") (pintype "passive"))
      (node (ref "F1") (pin "3") (pinfunction "38_3") (pintype "passive"))
      (node (ref "H5") (pin "2") (pinfunction "2_2") (pintype "passive"))
      (node (ref "R1") (pin "1") (pinfunction "1_1") (pintype "passive"))
      (node (ref "R27") (pin "1") (pinfunction "1_1") (pintype "passive"))
      (node (ref "U10") (pin "8") (pinfunction "8_8") (pintype "passive"))
      (node (ref "U4") (pin "20") (pinfunction "VCC_20") (pintype "power_in"))
      (node (ref "U6") (pin "4") (pinfunction "VCC_4") (pintype "passive"))
      (node (ref "U6") (pin "6") (pinfunction "VCC_6") (pintype "passive"))
      (node (ref "U9") (pin "2") (pinfunction "2_2") (pintype "passive"))
    )
    (net (code "39") (name "9V0") (class "Default")
      (node (ref "C14") (pin "2") (pinfunction "2_2") (pintype "passive"))
      (node (ref "C15") (pin "2") (pinfunction "2_2") (pintype "passive"))
      (node (ref "C3") (pin "2") (pinfunction "2_2") (pintype "passive"))
      (node (ref "C4") (pin "2") (pinfunction "2_2") (pintype "passive"))
      (node (ref "D1") (pin "2") (pinfunction "K_2") (pintype "passive"))
      (node (ref "D3") (pin "1") (pinfunction "A_1") (pintype "passive"))
      (node (ref "D4") (pin "2") (pinfunction "K_2") (pintype "passive"))
      (node (ref "U1") (pin "1") (pinfunction "IN_1") (pintype "power_in"))
      (node (ref "U2") (pin "3") (pinfunction "OUT_3") (pintype "power_in"))
      (node (ref "U3") (pin "1") (pinfunction "IN_1") (pintype "power_in"))
    )
    (net (code "40") (name "13V8") (class "Default")
      (node (ref "C1") (pin "1") (pinfunction "1_1") (pintype "passive"))
      (node (ref "C12") (pin "2") (pinfunction "2_2") (pintype "passive"))
      (node (ref "C13") (pin "2") (pinfunction "2_2") (pintype "passive"))
      (node (ref "D3") (pin "2") (pinfunction "K_2") (pintype "passive"))
      (node (ref "H1") (pin "3") (pinfunction "3_3") (pintype "passive"))
      (node (ref "P1") (pin "6") (pinfunction "6_6") (pintype "passive"))
      (node (ref "P2") (pin "6") (pinfunction "6_6") (pintype "passive"))
      (node (ref "P3") (pin "6") (pinfunction "6_6") (pintype "passive"))
      (node (ref "P4") (pin "6") (pinfunction "6_6") (pintype "passive"))
      (node (ref "U2") (pin "1") (pinfunction "IN_1") (pintype "power_in"))
    )
    (net (code "41") (name "ADS_VCC") (class "Default")
      (node (ref "C27") (pin "2") (pinfunction "2_2") (pintype "passive"))
      (node (ref "C28") (pin "1") (pinfunction "1_1") (pintype "passive"))
      (node (ref "C29") (pin "2") (pinfunction "2_2") (pintype "passive"))
      (node (ref "F3") (pin "1") (pinfunction "1_1") (pintype "passive"))
      (node (ref "R8") (pin "1") (pinfunction "1_1") (pintype "passive"))
      (node (ref "R9") (pin "1") (pinfunction "1_1") (pintype "passive"))
      (node (ref "U7") (pin "8") (pinfunction "VDD_8") (pintype "passive"))
    )
    (net (code "42") (name "ESP_BAT") (class "Default")
      (node (ref "C2") (pin "1") (pinfunction "1_1") (pintype "passive"))
      (node (ref "C21") (pin "2") (pinfunction "2_2") (pintype "passive"))
      (node (ref "H1") (pin "2") (pinfunction "2_2") (pintype "passive"))
      (node (ref "R7") (pin "2") (pinfunction "2_2") (pintype "passive"))
      (node (ref "U5") (pin "2") (pinfunction "IN_2") (pintype "passive"))
      (node (ref "U5") (pin "3") (pinfunction "IN_3") (pintype "passive"))
      (node (ref "U5") (pin "4") (pinfunction "IN_4") (pintype "passive"))
      (node (ref "U5") (pin "5") (pinfunction "IN_5") (pintype "passive"))
    )
    (net (code "43") (name "GNDD") (class "Default")
      (node (ref "C10") (pin "1") (pinfunction "1_1") (pintype "passive"))
      (node (ref "C18") (pin "1") (pinfunction "1_1") (pintype "passive"))
      (node (ref "C19") (pin "1") (pinfunction "1_1") (pintype "passive"))
      (node (ref "C20") (pin "2") (pinfunction "2_2") (pintype "passive"))
      (node (ref "C37") (pin "1") (pinfunction "1_1") (pintype "passive"))
      (node (ref "C39") (pin "1") (pinfunction "1_1") (pintype "passive"))
      (node (ref "C7") (pin "1") (pinfunction "1_1") (pintype "passive"))
      (node (ref "C8") (pin "1") (pinfunction "1_1") (pintype "passive"))
      (node (ref "C9") (pin "1") (pinfunction "1_1") (pintype "passive"))
      (node (ref "D2") (pin "2") (pinfunction "A_2") (pintype "passive"))
      (node (ref "F2") (pin "1") (pinfunction "38_1") (pintype "passive"))
      (node (ref "H5") (pin "1") (pinfunction "1_1") (pintype "passive"))
      (node (ref "P1") (pin "3") (pinfunction "3_3") (pintype "passive"))
      (node (ref "P2") (pin "3") (pinfunction "3_3") (pintype "passive"))
      (node (ref "P3") (pin "3") (pinfunction "3_3") (pintype "passive"))
      (node (ref "P4") (pin "3") (pinfunction "3_3") (pintype "passive"))
      (node (ref "R3") (pin "1") (pinfunction "1_1") (pintype "passive"))
      (node (ref "R5") (pin "1") (pinfunction "1_1") (pintype "passive"))
      (node (ref "S1") (pin "1") (pinfunction "1_1") (pintype "passive"))
      (node (ref "U10") (pin "5") (pinfunction "GND_5") (pintype "passive"))
      (node (ref "U4") (pin "1") (pinfunction "~{OE}1_1") (pintype "input"))
      (node (ref "U4") (pin "10") (pinfunction "GND_10") (pintype "power_in"))
      (node (ref "U4") (pin "19") (pinfunction "~{OE}2_19") (pintype "input"))
      (node (ref "U6") (pin "21") (pinfunction "GND_21") (pintype "passive"))
      (node (ref "U6") (pin "3") (pinfunction "GND_3") (pintype "passive"))
      (node (ref "U6") (pin "5") (pinfunction "GND_5") (pintype "passive"))
    )
    (net (code "44") (name "GND_ADS") (class "Default")
      (node (ref "C27") (pin "1") (pinfunction "1_1") (pintype "passive"))
      (node (ref "C28") (pin "2") (pinfunction "2_2") (pintype "passive"))
      (node (ref "C29") (pin "1") (pinfunction "1_1") (pintype "passive"))
      (node (ref "F4") (pin "1") (pinfunction "1_1") (pintype "passive"))
      (node (ref "R10") (pin "1") (pinfunction "1_1") (pintype "passive"))
      (node (ref "R11") (pin "1") (pinfunction "1_1") (pintype "passive"))
      (node (ref "U7") (pin "3") (pinfunction "GND_3") (pintype "passive"))
    )
    (net (code "45") (name "GND_BAT") (class "Default")
      (node (ref "C1") (pin "2") (pinfunction "2_2") (pintype "passive"))
      (node (ref "C12") (pin "1") (pinfunction "1_1") (pintype "passive"))
      (node (ref "C13") (pin "1") (pinfunction "1_1") (pintype "passive"))
      (node (ref "C14") (pin "1") (pinfunction "1_1") (pintype "passive"))
      (node (ref "C15") (pin "1") (pinfunction "1_1") (pintype "passive"))
      (node (ref "C16") (pin "1") (pinfunction "1_1") (pintype "passive"))
      (node (ref "C17") (pin "1") (pinfunction "1_1") (pintype "passive"))
      (node (ref "C25") (pin "1") (pinfunction "1_1") (pintype "passive"))
      (node (ref "C26") (pin "1") (pinfunction "1_1") (pintype "passive"))
      (node (ref "C3") (pin "1") (pinfunction "1_1") (pintype "passive"))
      (node (ref "C30") (pin "1") (pinfunction "1_1") (pintype "passive"))
      (node (ref "C31") (pin "2") (pinfunction "2_2") (pintype "passive"))
      (node (ref "C32") (pin "2") (pinfunction "2_2") (pintype "passive"))
      (node (ref "C33") (pin "2") (pinfunction "2_2") (pintype "passive"))
      (node (ref "C36") (pin "2") (pinfunction "2_2") (pintype "passive"))
      (node (ref "C4") (pin "1") (pinfunction "1_1") (pintype "passive"))
      (node (ref "C5") (pin "1") (pinfunction "1_1") (pintype "passive"))
      (node (ref "C6") (pin "1") (pinfunction "1_1") (pintype "passive"))
      (node (ref "D5") (pin "2") (pinfunction "A_2") (pintype "passive"))
      (node (ref "F2") (pin "3") (pinfunction "38_3") (pintype "passive"))
      (node (ref "F4") (pin "2") (pinfunction "2_2") (pintype "passive"))
      (node (ref "H1") (pin "4") (pinfunction "4_4") (pintype "passive"))
      (node (ref "P1") (pin "1") (pinfunction "1_1") (pintype "passive"))
      (node (ref "P2") (pin "1") (pinfunction "1_1") (pintype "passive"))
      (node (ref "P3") (pin "1") (pinfunction "1_1") (pintype "passive"))
      (node (ref "P4") (pin "1") (pinfunction "1_1") (pintype "passive"))
      (node (ref "U1") (pin "2") (pinfunction "GND_2") (pintype "power_in"))
      (node (ref "U2") (pin "2") (pinfunction "GND_2") (pintype "power_in"))
      (node (ref "U3") (pin "2") (pinfunction "GND_2") (pintype "power_in"))
    )
    (net (code "46") (name "GND_ESP") (class "Default")
      (node (ref "C2") (pin "2") (pinfunction "2_2") (pintype "passive"))
      (node (ref "C21") (pin "1") (pinfunction "1_1") (pintype "passive"))
      (node (ref "C22") (pin "1") (pinfunction "1_1") (pintype "passive"))
      (node (ref "C23") (pin "1") (pinfunction "1_1") (pintype "passive"))
      (node (ref "C24") (pin "1") (pinfunction "1_1") (pintype "passive"))
      (node (ref "C34") (pin "1") (pinfunction "1_1") (pintype "passive"))
      (node (ref "C35") (pin "1") (pinfunction "1_1") (pintype "passive"))
      (node (ref "C38") (pin "1") (pinfunction "1_1") (pintype "passive"))
      (node (ref "D6") (pin "2") (pinfunction "A_2") (pintype "passive"))
      (node (ref "H1") (pin "1") (pinfunction "1_1") (pintype "passive"))
      (node (ref "H3") (pin "1") (pinfunction "1_1") (pintype "passive"))
      (node (ref "Q1") (pin "1") (pinfunction "E_1") (pintype "passive"))
      (node (ref "Q2") (pin "1") (pinfunction "E_1") (pintype "passive"))
      (node (ref "R13") (pin "1") (pinfunction "1_1") (pintype "passive"))
      (node (ref "R21") (pin "2") (pinfunction "2_2") (pintype "passive"))
      (node (ref "R24") (pin "1") (pinfunction "1_1") (pintype "passive"))
      (node (ref "S2") (pin "1") (pinfunction "1_1") (pintype "passive"))
      (node (ref "U5") (pin "10") (pinfunction "GND_10") (pintype "passive"))
      (node (ref "U5") (pin "11") (pinfunction "SET_11") (pintype "passive"))
      (node (ref "U8") (pin "15") (pinfunction "GND_15") (pintype "passive"))
      (node (ref "U9") (pin "5") (pinfunction "GND_5") (pintype "passive"))
    )
    (net (code "47") (name "Net-(D1-A)") (class "Default")
      (node (ref "C5") (pin "2") (pinfunction "2_2") (pintype "passive"))
      (node (ref "C6") (pin "2") (pinfunction "2_2") (pintype "passive"))
      (node (ref "D1") (pin "1") (pinfunction "A_1") (pintype "passive"))
      (node (ref "F1") (pin "1") (pinfunction "38_1") (pintype "passive"))
      (node (ref "U1") (pin "3") (pinfunction "OUT_3") (pintype "power_in"))
    )
    (net (code "48") (name "Net-(F1-38-Pad2)") (class "Default")
      (node (ref "F1") (pin "2") (pinfunction "38_2") (pintype "passive"))
      (node (ref "F2") (pin "2") (pinfunction "38_2") (pintype "passive"))
    )
    (net (code "49") (name "Net-(H2-Pad1)") (class "Default")
      (node (ref "H2") (pin "1") (pinfunction "1_1") (pintype "passive"))
      (node (ref "R12") (pin "1") (pinfunction "1_1") (pintype "passive"))
      (node (ref "R22") (pin "1") (pinfunction "1_1") (pintype "passive"))
    )
    (net (code "50") (name "Net-(H4-Pad1)") (class "Default")
      (node (ref "H4") (pin "1") (pinfunction "1_1") (pintype "passive"))
      (node (ref "R25") (pin "2") (pinfunction "2_2") (pintype "passive"))
    )
    (net (code "51") (name "Net-(P1-Pad5)") (class "Default")
      (node (ref "P1") (pin "5") (pinfunction "5_5") (pintype "passive"))
      (node (ref "R14") (pin "1") (pinfunction "1_1") (pintype "passive"))
    )
    (net (code "52") (name "Net-(P2-Pad5)") (class "Default")
      (node (ref "P2") (pin "5") (pinfunction "5_5") (pintype "passive"))
      (node (ref "R17") (pin "1") (pinfunction "1_1") (pintype "passive"))
    )
    (net (code "53") (name "Net-(P3-Pad5)") (class "Default")
      (node (ref "P3") (pin "5") (pinfunction "5_5") (pintype "passive"))
      (node (ref "R18") (pin "1") (pinfunction "1_1") (pintype "passive"))
    )
    (net (code "54") (name "Net-(P4-Pad5)") (class "Default")
      (node (ref "P4") (pin "5") (pinfunction "5_5") (pintype "passive"))
      (node (ref "R23") (pin "1") (pinfunction "1_1") (pintype "passive"))
    )
    (net (code "55") (name "Net-(Q1-B)") (class "Default")
      (node (ref "Q1") (pin "2") (pinfunction "B_2") (pintype "passive"))
      (node (ref "R12") (pin "2") (pinfunction "2_2") (pintype "passive"))
      (node (ref "R13") (pin "2") (pinfunction "2_2") (pintype "passive"))
    )
    (net (code "56") (name "Net-(Q2-B)") (class "Default")
      (node (ref "Q2") (pin "2") (pinfunction "B_2") (pintype "passive"))
      (node (ref "R22") (pin "2") (pinfunction "2_2") (pintype "passive"))
      (node (ref "R24") (pin "2") (pinfunction "2_2") (pintype "passive"))
    )
    (net (code "57") (name "Net-(R28-Pad2)") (class "Default")
      (node (ref "R28") (pin "2") (pinfunction "2_2") (pintype "passive"))
      (node (ref "U9") (pin "3") (pinfunction "3_3") (pintype "passive"))
    )
    (net (code "58") (name "Net-(R29-Pad1)") (class "Default")
      (node (ref "R29") (pin "1") (pinfunction "1_1") (pintype "passive"))
      (node (ref "U10") (pin "3") (pinfunction "3_3") (pintype "passive"))
    )
    (net (code "59") (name "Net-(U4-A1)") (class "Default")
      (node (ref "R2") (pin "1") (pinfunction "1_1") (pintype "passive"))
      (node (ref "R3") (pin "2") (pinfunction "2_2") (pintype "passive"))
      (node (ref "U4") (pin "2") (pinfunction "A1_2") (pintype "input"))
      (node (ref "U4") (pin "3") (pinfunction "A2_3") (pintype "input"))
      (node (ref "U4") (pin "4") (pinfunction "A3_4") (pintype "input"))
      (node (ref "U4") (pin "5") (pinfunction "A4_5") (pintype "input"))
    )
    (net (code "60") (name "Net-(U4-A5)") (class "Default")
      (node (ref "R4") (pin "1") (pinfunction "1_1") (pintype "passive"))
      (node (ref "R5") (pin "2") (pinfunction "2_2") (pintype "passive"))
      (node (ref "U4") (pin "6") (pinfunction "A5_6") (pintype "input"))
      (node (ref "U4") (pin "7") (pinfunction "A6_7") (pintype "input"))
      (node (ref "U4") (pin "8") (pinfunction "A7_8") (pintype "input"))
      (node (ref "U4") (pin "9") (pinfunction "A8_9") (pintype "input"))
    )
    (net (code "61") (name "Net-(U5-RST)") (class "Default")
      (node (ref "R6") (pin "1") (pinfunction "1_1") (pintype "passive"))
      (node (ref "U5") (pin "6") (pinfunction "RST_6") (pintype "passive"))
    )
    (net (code "62") (name "Net-(U5-SHDN)") (class "Default")
      (node (ref "R7") (pin "1") (pinfunction "1_1") (pintype "passive"))
      (node (ref "U5") (pin "7") (pinfunction "SHDN_7") (pintype "passive"))
    )
    (net (code "63") (name "Net-(U6-AREF)") (class "Default")
      (node (ref "C26") (pin "2") (pinfunction "2_2") (pintype "passive"))
      (node (ref "U6") (pin "20") (pinfunction "AREF_20") (pintype "passive"))
    )
    (net (code "64") (name "Net-(U7-ADDR)") (class "Default")
      (node (ref "R10") (pin "2") (pinfunction "2_2") (pintype "passive"))
      (node (ref "U7") (pin "1") (pinfunction "ADDR_1") (pintype "passive"))
    )
    (net (code "65") (name "Net-(U8-EN(CH-PD))") (class "Default")
      (node (ref "R16") (pin "1") (pinfunction "1_1") (pintype "passive"))
      (node (ref "U8") (pin "3") (pinfunction "EN(CH-PD)_3") (pintype "passive"))
    )
    (net (code "66") (name "Net-(U8-GPIO2)") (class "Default")
      (node (ref "R19") (pin "1") (pinfunction "1_1") (pintype "passive"))
      (node (ref "U8") (pin "17") (pinfunction "GPIO2_17") (pintype "passive"))
    )
    (net (code "67") (name "Net-(U8-GPIO15)") (class "Default")
      (node (ref "R21") (pin "1") (pinfunction "1_1") (pintype "passive"))
      (node (ref "U8") (pin "16") (pinfunction "GPIO15_16") (pintype "passive"))
    )
    (net (code "68") (name "Net-(U8-~{RST})") (class "Default")
      (node (ref "C35") (pin "2") (pinfunction "2_2") (pintype "passive"))
      (node (ref "R15") (pin "2") (pinfunction "2_2") (pintype "passive"))
      (node (ref "S2") (pin "2") (pinfunction "2_2") (pintype "passive"))
      (node (ref "U8") (pin "1") (pinfunction "~{RST}_1") (pintype "passive"))
    )
    (net (code "69") (name "unconnected-(H3-Pad2)") (class "Default")
      (node (ref "H3") (pin "2") (pinfunction "2_2") (pintype "passive+no_connect"))
    )
    (net (code "70") (name "unconnected-(H3-Pad4)") (class "Default")
      (node (ref "H3") (pin "4") (pinfunction "4_4") (pintype "passive+no_connect"))
    )
    (net (code "71") (name "unconnected-(H3-Pad6)") (class "Default")
      (node (ref "H3") (pin "6") (pinfunction "6_6") (pintype "passive+no_connect"))
    )
    (net (code "72") (name "unconnected-(U5-NC-Pad1)") (class "Default")
      (node (ref "U5") (pin "1") (pinfunction "NC_1") (pintype "passive+no_connect"))
    )
    (net (code "73") (name "unconnected-(U5-NC-Pad8)") (class "Default")
      (node (ref "U5") (pin "8") (pinfunction "NC_8") (pintype "passive+no_connect"))
    )
    (net (code "74") (name "unconnected-(U5-NC-Pad9)") (class "Default")
      (node (ref "U5") (pin "9") (pinfunction "NC_9") (pintype "passive+no_connect"))
    )
    (net (code "75") (name "unconnected-(U5-NC-Pad16)") (class "Default")
      (node (ref "U5") (pin "16") (pinfunction "NC_16") (pintype "passive+no_connect"))
    )
    (net (code "76") (name "unconnected-(U8-ADC-Pad2)") (class "Default")
      (node (ref "U8") (pin "2") (pinfunction "ADC_2") (pintype "passive+no_connect"))
    )
    (net (code "77") (name "unconnected-(U8-CS0-Pad9)") (class "Default")
      (node (ref "U8") (pin "9") (pinfunction "CS0_9") (pintype "passive+no_connect"))
    )
    (net (code "78") (name "unconnected-(U8-GPIO4-Pad19)") (class "Default")
      (node (ref "U8") (pin "19") (pinfunction "GPIO4_19") (pintype "passive+no_connect"))
    )
    (net (code "79") (name "unconnected-(U8-GPIO5-Pad20)") (class "Default")
      (node (ref "U8") (pin "20") (pinfunction "GPIO5_20") (pintype "passive+no_connect"))
    )
    (net (code "80") (name "unconnected-(U8-GPIO9-Pad11)") (class "Default")
      (node (ref "U8") (pin "11") (pinfunction "GPIO9_11") (pintype "passive+no_connect"))
    )
    (net (code "81") (name "unconnected-(U8-GPIO10-Pad12)") (class "Default")
      (node (ref "U8") (pin "12") (pinfunction "GPIO10_12") (pintype "passive+no_connect"))
    )
    (net (code "82") (name "unconnected-(U8-GPIO12-Pad6)") (class "Default")
      (node (ref "U8") (pin "6") (pinfunction "GPIO12_6") (pintype "passive+no_connect"))
    )
    (net (code "83") (name "unconnected-(U8-GPIO13-Pad7)") (class "Default")
      (node (ref "U8") (pin "7") (pinfunction "GPIO13_7") (pintype "passive+no_connect"))
    )
    (net (code "84") (name "unconnected-(U8-GPIO14-Pad5)") (class "Default")
      (node (ref "U8") (pin "5") (pinfunction "GPIO14_5") (pintype "passive+no_connect"))
    )
    (net (code "85") (name "unconnected-(U8-GPIO16-Pad4)") (class "Default")
      (node (ref "U8") (pin "4") (pinfunction "GPIO16_4") (pintype "passive+no_connect"))
    )
    (net (code "86") (name "unconnected-(U8-MISO-Pad10)") (class "Default")
      (node (ref "U8") (pin "10") (pinfunction "MISO_10") (pintype "passive+no_connect"))
    )
    (net (code "87") (name "unconnected-(U8-MOSI-Pad13)") (class "Default")
      (node (ref "U8") (pin "13") (pinfunction "MOSI_13") (pintype "passive+no_connect"))
    )
    (net (code "88") (name "unconnected-(U8-SCLK-Pad14)") (class "Default")
      (node (ref "U8") (pin "14") (pinfunction "SCLK_14") (pintype "passive+no_connect"))
    )
    (net (code "89") (name "unconnected-(U9-Pad1)") (class "Default")
      (node (ref "U9") (pin "1") (pinfunction "1_1") (pintype "passive+no_connect"))
    )
    (net (code "90") (name "unconnected-(U9-Pad4)") (class "Default")
      (node (ref "U9") (pin "4") (pinfunction "4_4") (pintype "passive+no_connect"))
    )
    (net (code "91") (name "unconnected-(U10-Pad1)") (class "Default")
      (node (ref "U10") (pin "1") (pinfunction "1_1") (pintype "passive+no_connect"))
    )
    (net (code "92") (name "unconnected-(U10-Pad4)") (class "Default")
      (node (ref "U10") (pin "4") (pinfunction "4_4") (pintype "passive+no_connect"))
    )
    (net (code "93") (name "unconnected-(U10-Pad7)") (class "Default")
      (node (ref "U10") (pin "7") (pinfunction "7_7") (pintype "passive+no_connect"))
    )
    (net (code "94") (name "unconnected-(W1-Wall-Pad1)") (class "Default")
      (node (ref "W1") (pin "1") (pinfunction "Wall_1") (pintype "passive"))
    )
    (net (code "95") (name "unconnected-(W2-Wall-Pad1)") (class "Default")
      (node (ref "W2") (pin "1") (pinfunction "Wall_1") (pintype "passive"))
    )
  )
)
